# schematic.net
KiCad netlist of a schematic drawn in EAGLE
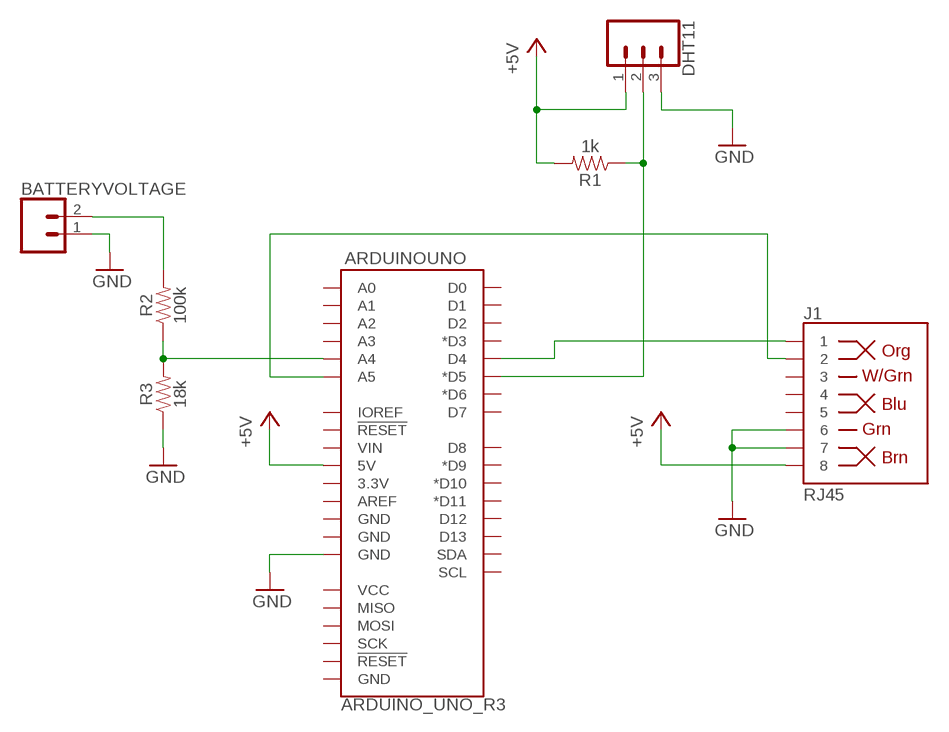
[diagram p0: schematic, sheet 1]

(export (version "E")
  (design (tool "Eeschema 10.0.6"))
  (components
    (comp (ref "ARDUINOUNO")
      (value "ARDUINO_UNO_R3")
      (footprint "eagle-import:ARDUINO_R3")
      (libsource (lib "eagle-import") (part "ARDUINO_UNO_R3"))
    )
    (comp (ref "BATTERYVOLTAGE")
      (value "CONN_02")
      (footprint "eagle-import:1X02")
      (libsource (lib "eagle-import") (part "CONN_02"))
    )
    (comp (ref "DHT11")
      (value "CONN_03")
      (footprint "eagle-import:1X03")
      (libsource (lib "eagle-import") (part "CONN_03"))
    )
    (comp (ref "J1")
      (value "RJ45")
      (footprint "eagle-import:RJ45-8")
      (libsource (lib "eagle-import") (part "RJ45-8"))
    )
    (comp (ref "R1")
      (value "1k")
      (footprint "eagle-import:AXIAL-0.3")
      (libsource (lib "eagle-import") (part "1KOHM-HORIZ-1/4W-1%"))
    )
    (comp (ref "R2")
      (value "100k")
      (footprint "eagle-import:AXIAL-0.3")
      (libsource (lib "eagle-import") (part "1KOHM-HORIZ-1/4W-1%"))
    )
    (comp (ref "R3")
      (value "18k")
      (footprint "eagle-import:AXIAL-0.3")
      (libsource (lib "eagle-import") (part "1KOHM-HORIZ-1/4W-1%"))
    )
  )
  (nets
    (net (code "1") (name "+5V") (class "Default")
      (node (ref "ARDUINOUNO") (pin "5V") (pinfunction "5V_5V") (pintype "bidirectional"))
      (node (ref "DHT11") (pin "1") (pinfunction "1_1") (pintype "passive"))
      (node (ref "J1") (pin "8") (pinfunction "8_8") (pintype "bidirectional"))
      (node (ref "R1") (pin "P$2") (pinfunction "2_P$2") (pintype "passive"))
    )
    (net (code "2") (name "GND") (class "Default")
      (node (ref "ARDUINOUNO") (pin "GND@2") (pinfunction "GND_GND@2") (pintype "bidirectional"))
      (node (ref "BATTERYVOLTAGE") (pin "1") (pinfunction "1_1") (pintype "passive"))
      (node (ref "DHT11") (pin "3") (pinfunction "3_3") (pintype "passive"))
      (node (ref "J1") (pin "6") (pinfunction "6_6") (pintype "bidirectional"))
      (node (ref "J1") (pin "7") (pinfunction "7_7") (pintype "bidirectional"))
      (node (ref "R3") (pin "P$1") (pinfunction "1_P$1") (pintype "passive"))
    )
    (net (code "3") (name "Net-(ARDUINOUNO-*D5)") (class "Default")
      (node (ref "ARDUINOUNO") (pin "D5") (pinfunction "*D5_D5") (pintype "bidirectional"))
      (node (ref "DHT11") (pin "2") (pinfunction "2_2") (pintype "passive"))
      (node (ref "R1") (pin "P$1") (pinfunction "1_P$1") (pintype "passive"))
    )
    (net (code "4") (name "Net-(ARDUINOUNO-PadA5)") (class "Default")
      (node (ref "ARDUINOUNO") (pin "A5") (pinfunction "A5_A5") (pintype "bidirectional"))
      (node (ref "J1") (pin "2") (pinfunction "2_2") (pintype "bidirectional"))
    )
    (net (code "5") (name "Net-(ARDUINOUNO-PadD4)") (class "Default")
      (node (ref "ARDUINOUNO") (pin "D4") (pinfunction "D4_D4") (pintype "bidirectional"))
      (node (ref "J1") (pin "1") (pinfunction "1_1") (pintype "bidirectional"))
    )
    (net (code "6") (name "Net-(R2-1)") (class "Default")
      (node (ref "ARDUINOUNO") (pin "A4") (pinfunction "A4_A4") (pintype "bidirectional"))
      (node (ref "R2") (pin "P$1") (pinfunction "1_P$1") (pintype "passive"))
      (node (ref "R3") (pin "P$2") (pinfunction "2_P$2") (pintype "passive"))
    )
    (net (code "7") (name "Net-(R2-2)") (class "Default")
      (node (ref "BATTERYVOLTAGE") (pin "2") (pinfunction "2_2") (pintype "passive"))
      (node (ref "R2") (pin "P$2") (pinfunction "2_P$2") (pintype "passive"))
    )
    (net (code "8") (name "unconnected-(ARDUINOUNO-*D3-PadD3)") (class "Default")
      (node (ref "ARDUINOUNO") (pin "D3") (pinfunction "*D3_D3") (pintype "bidirectional"))
    )
    (net (code "9") (name "unconnected-(ARDUINOUNO-*D6-PadD6)") (class "Default")
      (node (ref "ARDUINOUNO") (pin "D6") (pinfunction "*D6_D6") (pintype "bidirectional"))
    )
    (net (code "10") (name "unconnected-(ARDUINOUNO-*D9-PadD9)") (class "Default")
      (node (ref "ARDUINOUNO") (pin "D9") (pinfunction "*D9_D9") (pintype "bidirectional"))
    )
    (net (code "11") (name "unconnected-(ARDUINOUNO-*D10-PadD10)") (class "Default")
      (node (ref "ARDUINOUNO") (pin "D10") (pinfunction "*D10_D10") (pintype "bidirectional"))
    )
    (net (code "12") (name "unconnected-(ARDUINOUNO-*D11-PadD11)") (class "Default")
      (node (ref "ARDUINOUNO") (pin "D11") (pinfunction "*D11_D11") (pintype "bidirectional"))
    )
    (net (code "13") (name "unconnected-(ARDUINOUNO-GND-PadGND@1)") (class "Default")
      (node (ref "ARDUINOUNO") (pin "GND@1") (pinfunction "GND_GND@1") (pintype "bidirectional"))
    )
    (net (code "14") (name "unconnected-(ARDUINOUNO-GND-PadGND@3)") (class "Default")
      (node (ref "ARDUINOUNO") (pin "GND@3") (pinfunction "GND_GND@3") (pintype "bidirectional"))
    )
    (net (code "15") (name "unconnected-(ARDUINOUNO-GND-PadGND@4)") (class "Default")
      (node (ref "ARDUINOUNO") (pin "GND@4") (pinfunction "GND_GND@4") (pintype "bidirectional"))
    )
    (net (code "16") (name "unconnected-(ARDUINOUNO-Pad3.3V)") (class "Default")
      (node (ref "ARDUINOUNO") (pin "3.3V") (pinfunction "3.3V_3.3V") (pintype "bidirectional"))
    )
    (net (code "17") (name "unconnected-(ARDUINOUNO-PadA0)") (class "Default")
      (node (ref "ARDUINOUNO") (pin "A0") (pinfunction "A0_A0") (pintype "bidirectional"))
    )
    (net (code "18") (name "unconnected-(ARDUINOUNO-PadA1)") (class "Default")
      (node (ref "ARDUINOUNO") (pin "A1") (pinfunction "A1_A1") (pintype "bidirectional"))
    )
    (net (code "19") (name "unconnected-(ARDUINOUNO-PadA2)") (class "Default")
      (node (ref "ARDUINOUNO") (pin "A2") (pinfunction "A2_A2") (pintype "bidirectional"))
    )
    (net (code "20") (name "unconnected-(ARDUINOUNO-PadA3)") (class "Default")
      (node (ref "ARDUINOUNO") (pin "A3") (pinfunction "A3_A3") (pintype "bidirectional"))
    )
    (net (code "21") (name "unconnected-(ARDUINOUNO-PadAREF)") (class "Default")
      (node (ref "ARDUINOUNO") (pin "AREF") (pinfunction "AREF_AREF") (pintype "bidirectional"))
    )
    (net (code "22") (name "unconnected-(ARDUINOUNO-PadD0)") (class "Default")
      (node (ref "ARDUINOUNO") (pin "D0") (pinfunction "D0_D0") (pintype "bidirectional"))
    )
    (net (code "23") (name "unconnected-(ARDUINOUNO-PadD1)") (class "Default")
      (node (ref "ARDUINOUNO") (pin "D1") (pinfunction "D1_D1") (pintype "bidirectional"))
    )
    (net (code "24") (name "unconnected-(ARDUINOUNO-PadD2)") (class "Default")
      (node (ref "ARDUINOUNO") (pin "D2") (pinfunction "D2_D2") (pintype "bidirectional"))
    )
    (net (code "25") (name "unconnected-(ARDUINOUNO-PadD7)") (class "Default")
      (node (ref "ARDUINOUNO") (pin "D7") (pinfunction "D7_D7") (pintype "bidirectional"))
    )
    (net (code "26") (name "unconnected-(ARDUINOUNO-PadD8)") (class "Default")
      (node (ref "ARDUINOUNO") (pin "D8") (pinfunction "D8_D8") (pintype "bidirectional"))
    )
    (net (code "27") (name "unconnected-(ARDUINOUNO-PadD12)") (class "Default")
      (node (ref "ARDUINOUNO") (pin "D12") (pinfunction "D12_D12") (pintype "bidirectional"))
    )
    (net (code "28") (name "unconnected-(ARDUINOUNO-PadD13)") (class "Default")
      (node (ref "ARDUINOUNO") (pin "D13") (pinfunction "D13_D13") (pintype "bidirectional"))
    )
    (net (code "29") (name "unconnected-(ARDUINOUNO-PadIOREF)") (class "Default")
      (node (ref "ARDUINOUNO") (pin "IOREF") (pinfunction "IOREF_IOREF") (pintype "bidirectional"))
    )
    (net (code "30") (name "unconnected-(ARDUINOUNO-PadMISO)") (class "Default")
      (node (ref "ARDUINOUNO") (pin "MISO") (pinfunction "MISO_MISO") (pintype "bidirectional"))
    )
    (net (code "31") (name "unconnected-(ARDUINOUNO-PadMOSI)") (class "Default")
      (node (ref "ARDUINOUNO") (pin "MOSI") (pinfunction "MOSI_MOSI") (pintype "bidirectional"))
    )
    (net (code "32") (name "unconnected-(ARDUINOUNO-PadSCK)") (class "Default")
      (node (ref "ARDUINOUNO") (pin "SCK") (pinfunction "SCK_SCK") (pintype "bidirectional"))
    )
    (net (code "33") (name "unconnected-(ARDUINOUNO-PadSCL)") (class "Default")
      (node (ref "ARDUINOUNO") (pin "SCL") (pinfunction "SCL_SCL") (pintype "bidirectional"))
    )
    (net (code "34") (name "unconnected-(ARDUINOUNO-PadSDA)") (class "Default")
      (node (ref "ARDUINOUNO") (pin "SDA") (pinfunction "SDA_SDA") (pintype "bidirectional"))
    )
    (net (code "35") (name "unconnected-(ARDUINOUNO-PadVCC)") (class "Default")
      (node (ref "ARDUINOUNO") (pin "VCC") (pinfunction "VCC_VCC") (pintype "bidirectional"))
    )
    (net (code "36") (name "unconnected-(ARDUINOUNO-PadVIN)") (class "Default")
      (node (ref "ARDUINOUNO") (pin "VIN") (pinfunction "VIN_VIN") (pintype "bidirectional"))
    )
    (net (code "37") (name "unconnected-(ARDUINOUNO-~{RESET}-PadRESET@1)") (class "Default")
      (node (ref "ARDUINOUNO") (pin "RESET@1") (pinfunction "~{RESET}_RESET@1") (pintype "bidirectional"))
    )
    (net (code "38") (name "unconnected-(ARDUINOUNO-~{RESET}-PadRESET@2)") (class "Default")
      (node (ref "ARDUINOUNO") (pin "RESET@2") (pinfunction "~{RESET}_RESET@2") (pintype "bidirectional"))
    )
    (net (code "39") (name "unconnected-(J1-Pad3)") (class "Default")
      (node (ref "J1") (pin "3") (pinfunction "3_3") (pintype "bidirectional"))
    )
    (net (code "40") (name "unconnected-(J1-Pad4)") (class "Default")
      (node (ref "J1") (pin "4") (pinfunction "4_4") (pintype "bidirectional"))
    )
    (net (code "41") (name "unconnected-(J1-Pad5)") (class "Default")
      (node (ref "J1") (pin "5") (pinfunction "5_5") (pintype "bidirectional"))
    )
  )
)
